# MCU089A_Connectors.net
KiCad netlist of a schematic drawn in Altium Designer
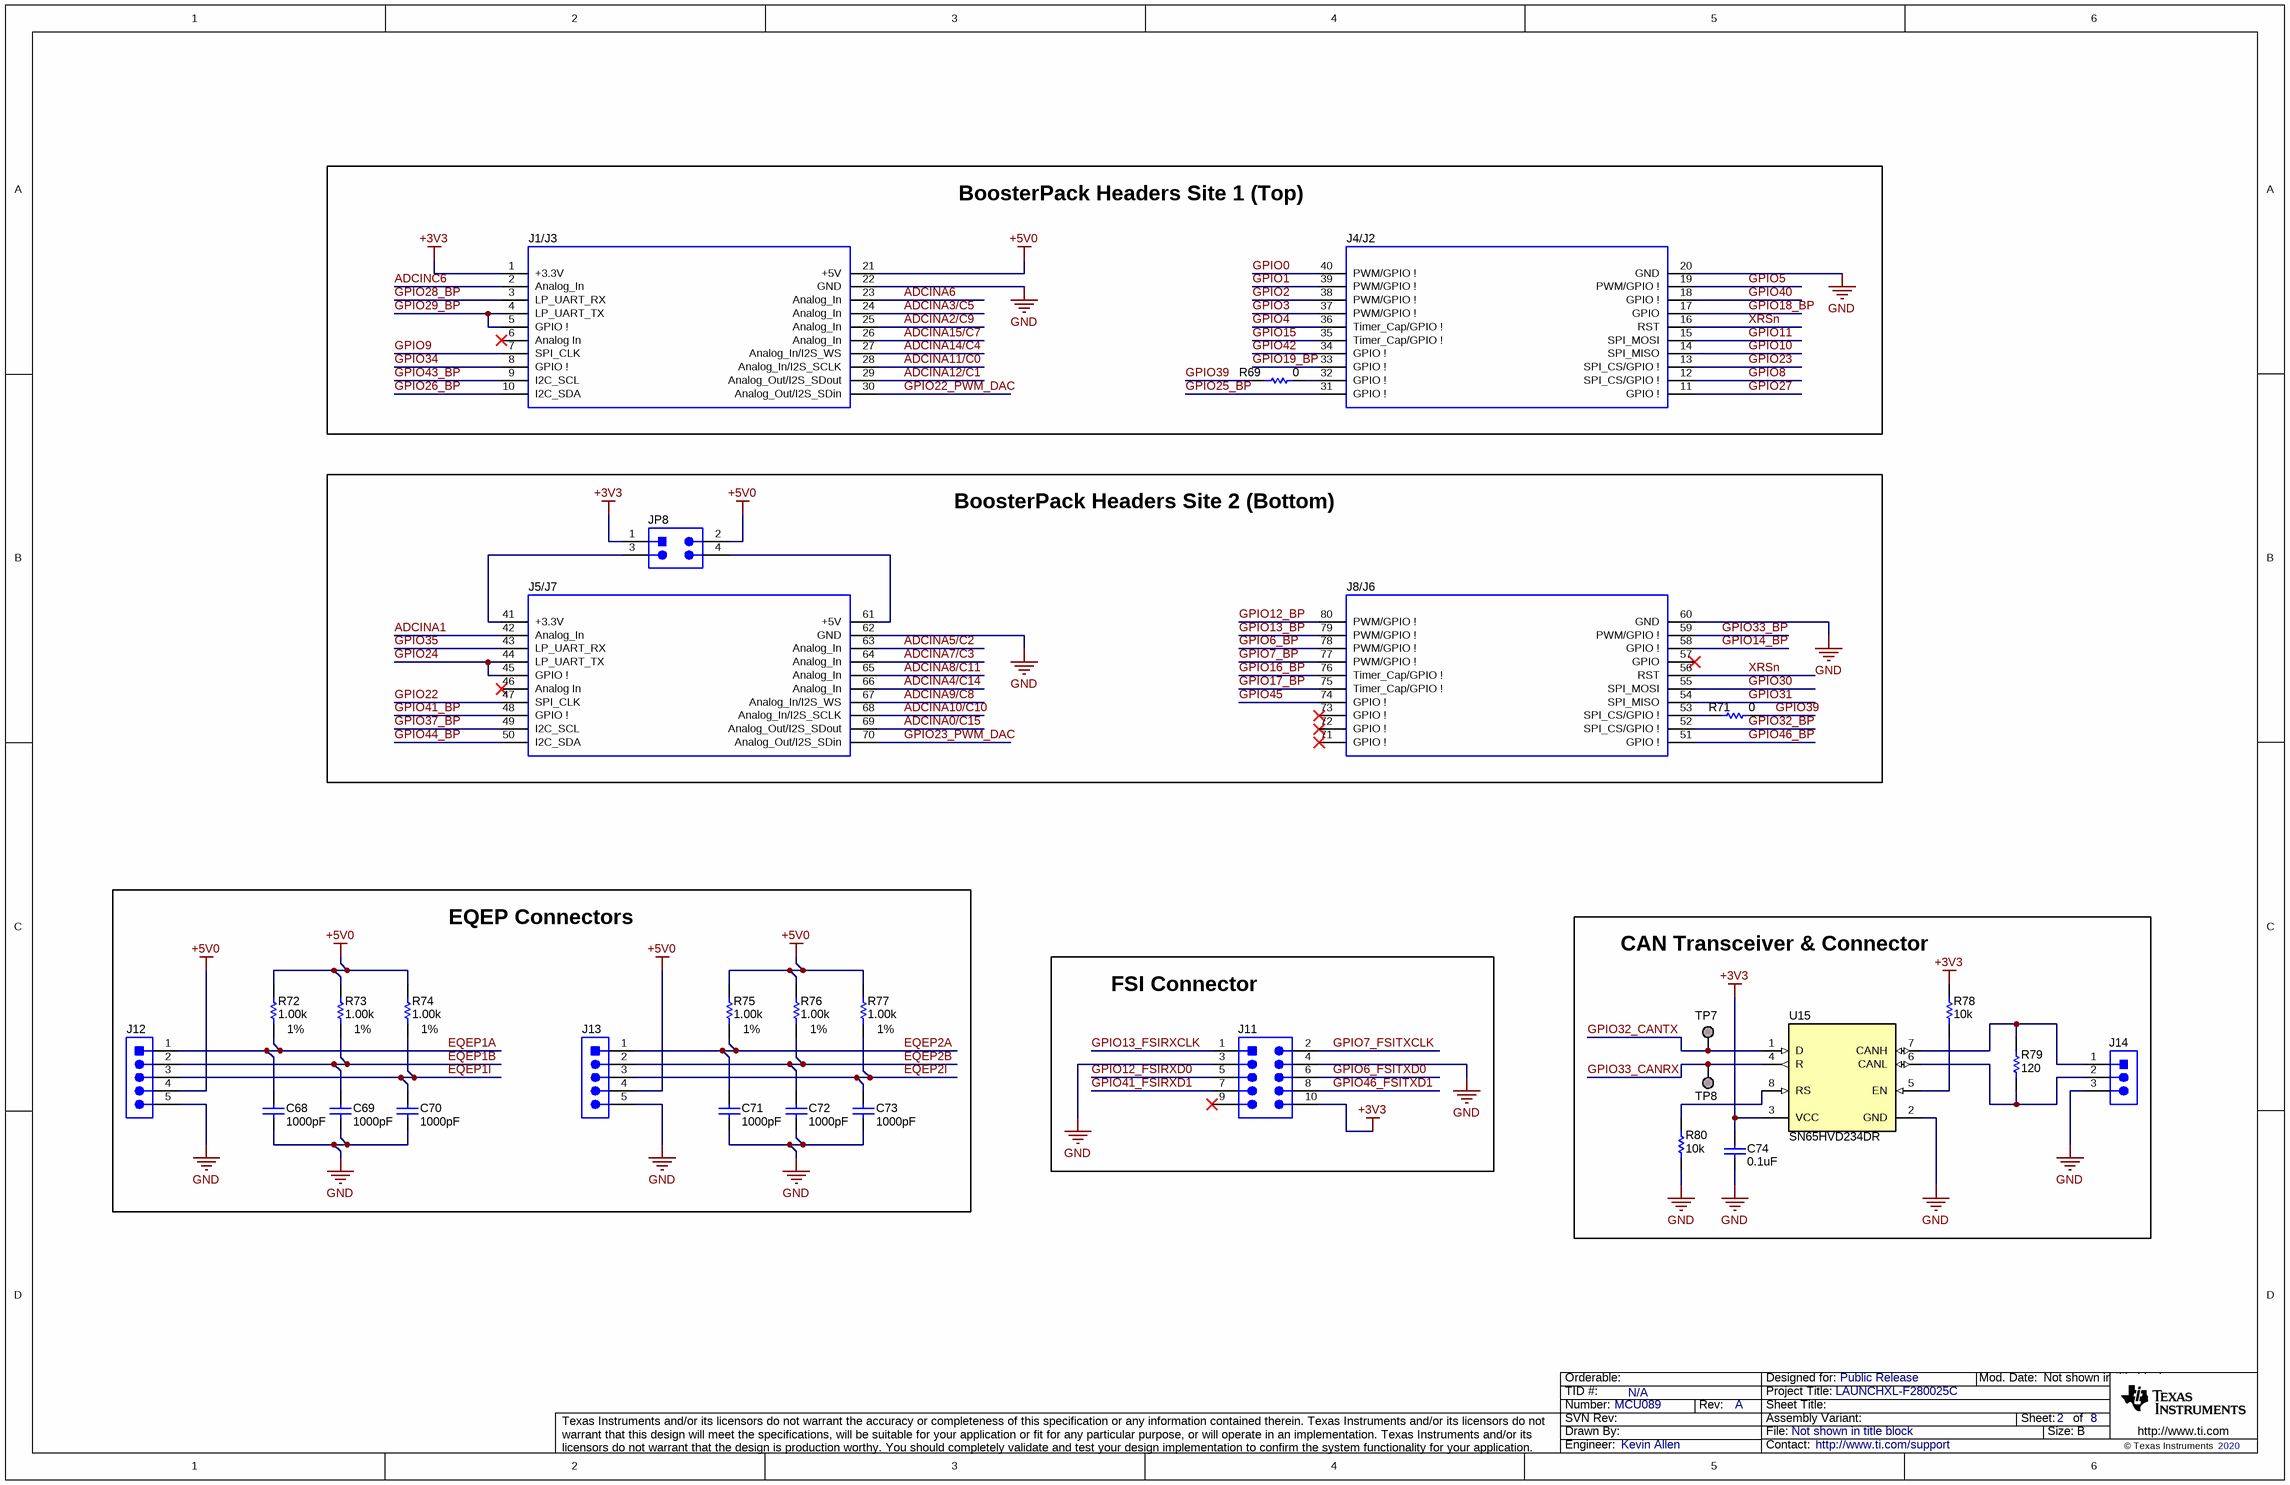
[diagram p0: MCU089A_Connectors.SchDoc]

(export (version "E")
  (design (tool "Eeschema 10.0.6"))
  (components
    (comp (ref "C68")
      (value "885012205061")
      (footprint "0402")
      (description "CAP, CERM, 1000 pF, 50 V, +/- 10%, X7R, 0402")
      (fields
        (field (name "VALUEDISPLAYED") "1000pF")
        (field (name "MANUFACTURER") "Wurth Elektronik")
        (field (name "PUBLISHER") "Texas Instruments")
      )
      (libsource (lib "Altium Vault - TI") (part "Capacitor"))
    )
    (comp (ref "C69")
      (value "885012205061")
      (footprint "0402")
      (description "CAP, CERM, 1000 pF, 50 V, +/- 10%, X7R, 0402")
      (fields
        (field (name "VALUEDISPLAYED") "1000pF")
        (field (name "MANUFACTURER") "Wurth Elektronik")
        (field (name "PUBLISHER") "Texas Instruments")
      )
      (libsource (lib "Altium Vault - TI") (part "Capacitor"))
    )
    (comp (ref "C70")
      (value "885012205061")
      (footprint "0402")
      (description "CAP, CERM, 1000 pF, 50 V, +/- 10%, X7R, 0402")
      (fields
        (field (name "VALUEDISPLAYED") "1000pF")
        (field (name "MANUFACTURER") "Wurth Elektronik")
        (field (name "PUBLISHER") "Texas Instruments")
      )
      (libsource (lib "Altium Vault - TI") (part "Capacitor"))
    )
    (comp (ref "C71")
      (value "885012205061")
      (footprint "0402")
      (description "CAP, CERM, 1000 pF, 50 V, +/- 10%, X7R, 0402")
      (fields
        (field (name "VALUEDISPLAYED") "1000pF")
        (field (name "MANUFACTURER") "Wurth Elektronik")
        (field (name "PUBLISHER") "Texas Instruments")
      )
      (libsource (lib "Altium Vault - TI") (part "Capacitor"))
    )
    (comp (ref "C72")
      (value "885012205061")
      (footprint "0402")
      (description "CAP, CERM, 1000 pF, 50 V, +/- 10%, X7R, 0402")
      (fields
        (field (name "VALUEDISPLAYED") "1000pF")
        (field (name "MANUFACTURER") "Wurth Elektronik")
        (field (name "PUBLISHER") "Texas Instruments")
      )
      (libsource (lib "Altium Vault - TI") (part "Capacitor"))
    )
    (comp (ref "C73")
      (value "885012205061")
      (footprint "0402")
      (description "CAP, CERM, 1000 pF, 50 V, +/- 10%, X7R, 0402")
      (fields
        (field (name "VALUEDISPLAYED") "1000pF")
        (field (name "MANUFACTURER") "Wurth Elektronik")
        (field (name "PUBLISHER") "Texas Instruments")
      )
      (libsource (lib "Altium Vault - TI") (part "Capacitor"))
    )
    (comp (ref "C74")
      (value "GRM155R71A104KA01D")
      (footprint "0402")
      (description "CAP, CERM, 0.1 uF, 10 V, +/- 10%, X7R, 0402")
      (fields
        (field (name "VALUEDISPLAYED") "0.1uF")
        (field (name "MANUFACTURER") "MuRata")
        (field (name "PUBLISHER") "Texas Instruments")
      )
      (libsource (lib "Altium Vault - TI") (part "Capacitor"))
    )
    (comp (ref "J1/J3")
      (value "SSQ-110-03-T-D")
      (footprint "BoosterPack_40pin_J1J3")
      (description "Receptacle, 2.54mm, 10x2, Tin, TH")
      (fields (field (name "ALTERNATE PARTNUMBER") "CRD-081413-A-G") (field (name "MANUFACTURER") "Samtec"))
      (libsource (lib "Altium Vault - TI") (part "BoosterPack_40pin_J1J3"))
    )
    (comp (ref "J4/J2")
      (value "SSQ-110-03-T-D")
      (footprint "BoosterPack_40pin_J2J4")
      (description "Receptacle, 2.54mm, 10x2, Tin, TH")
      (fields (field (name "ALTERNATE PARTNUMBER") "CRD-081413-A-G") (field (name "MANUFACTURER") "Samtec"))
      (libsource (lib "Altium Vault - TI") (part "BoosterPack_40pin_J2J4"))
    )
    (comp (ref "J5/J7")
      (value "SSQ-110-03-T-D")
      (footprint "BoosterPack_40pin_J5J7")
      (description "Receptacle, 2.54mm, 10x2, Tin, TH")
      (fields (field (name "ALTERNATE PARTNUMBER") "CRD-081413-A-G") (field (name "MANUFACTURER") "Samtec"))
      (libsource (lib "Altium Vault - TI") (part "BoosterPack_40pin_J5J7"))
    )
    (comp (ref "J8/J6")
      (value "SSQ-110-03-T-D")
      (footprint "BoosterPack_40pin_J6J8")
      (description "Receptacle, 2.54mm, 10x2, Tin, TH")
      (fields (field (name "ALTERNATE PARTNUMBER") "CRD-081413-A-G") (field (name "MANUFACTURER") "Samtec"))
      (libsource (lib "Altium Vault - TI") (part "BoosterPack_40pin_J6J8"))
    )
    (comp (ref "J11")
      (value "TSW-105-07-G-D")
      (footprint "TSW-105-07-G-D")
      (description "Header, 100mil, 5x2, Gold, TH")
      (fields (field (name "MANUFACTURER") "Samtec"))
      (libsource (lib "Altium Vault - TI") (part "Header_5x2"))
    )
    (comp (ref "J12")
      (value "TSW-105-07-G-S")
      (footprint "TSW-105-07-X-S")
      (description "Header, 100mil, 5x1, Gold, TH")
      (fields (field (name "MANUFACTURER") "Samtec") (field (name "PUBLISHER") "Texas Instruments"))
      (libsource (lib "Altium Vault - TI") (part "Header_5x1"))
    )
    (comp (ref "J13")
      (value "TSW-105-07-G-S")
      (footprint "TSW-105-07-X-S")
      (description "Header, 100mil, 5x1, Gold, TH")
      (fields (field (name "MANUFACTURER") "Samtec") (field (name "PUBLISHER") "Texas Instruments"))
      (libsource (lib "Altium Vault - TI") (part "Header_5x1"))
    )
    (comp (ref "J14")
      (value "61300311121")
      (footprint "WURTH_61300311121")
      (description "Header, 2.54 mm, 3x1, Gold, TH")
      (fields (field (name "MANUFACTURER") "Wurth Elektronik") (field (name "PUBLISHER") "Texas Instruments"))
      (libsource (lib "Altium Vault - TI") (part "CMP-0054796-1"))
    )
    (comp (ref "JP8")
      (value "TSW-102-07-G-D")
      (footprint "TSW-102-07-G-D")
      (description "Header, 100mil, 2x2, Gold, TH")
      (fields (field (name "MANUFACTURER") "Samtec") (field (name "PUBLISHER") "Texas Instruments"))
      (libsource (lib "Altium Vault - TI") (part "Header_2x2"))
    )
    (comp (ref "R69")
      (value "CRCW06030000Z0EA")
      (footprint "0603")
      (description "RES, 0, 5%, 0.1 W, AEC-Q200 Grade 0, 0603")
      (fields (field (name "VALUEDISPLAYED") "0") (field (name "MANUFACTURER") "Vishay-Dale"))
      (libsource (lib "Altium Vault - TI") (part "Resistor"))
    )
    (comp (ref "R71")
      (value "CRCW06030000Z0EA")
      (footprint "0603")
      (description "RES, 0, 5%, 0.1 W, AEC-Q200 Grade 0, 0603")
      (fields (field (name "VALUEDISPLAYED") "0") (field (name "MANUFACTURER") "Vishay-Dale"))
      (libsource (lib "Altium Vault - TI") (part "Resistor"))
    )
    (comp (ref "R72")
      (value "CRCW04021K00FKED")
      (footprint "0402")
      (description "RES, 1.00 k, 1%, 0.063 W, AEC-Q200 Grade 0, 0402")
      (fields
        (field (name "VALUEDISPLAYED") "1.00k")
        (field (name "MANUFACTURER") "Vishay-Dale")
        (field (name "VALUE1") "1%")
      )
      (libsource (lib "Altium Vault - TI") (part "Resistor"))
    )
    (comp (ref "R73")
      (value "CRCW04021K00FKED")
      (footprint "0402")
      (description "RES, 1.00 k, 1%, 0.063 W, AEC-Q200 Grade 0, 0402")
      (fields
        (field (name "VALUEDISPLAYED") "1.00k")
        (field (name "MANUFACTURER") "Vishay-Dale")
        (field (name "VALUE1") "1%")
      )
      (libsource (lib "Altium Vault - TI") (part "Resistor"))
    )
    (comp (ref "R74")
      (value "CRCW04021K00FKED")
      (footprint "0402")
      (description "RES, 1.00 k, 1%, 0.063 W, AEC-Q200 Grade 0, 0402")
      (fields
        (field (name "VALUEDISPLAYED") "1.00k")
        (field (name "MANUFACTURER") "Vishay-Dale")
        (field (name "VALUE1") "1%")
      )
      (libsource (lib "Altium Vault - TI") (part "Resistor"))
    )
    (comp (ref "R75")
      (value "CRCW04021K00FKED")
      (footprint "0402")
      (description "RES, 1.00 k, 1%, 0.063 W, AEC-Q200 Grade 0, 0402")
      (fields
        (field (name "VALUEDISPLAYED") "1.00k")
        (field (name "MANUFACTURER") "Vishay-Dale")
        (field (name "VALUE1") "1%")
      )
      (libsource (lib "Altium Vault - TI") (part "Resistor"))
    )
    (comp (ref "R76")
      (value "CRCW04021K00FKED")
      (footprint "0402")
      (description "RES, 1.00 k, 1%, 0.063 W, AEC-Q200 Grade 0, 0402")
      (fields
        (field (name "VALUEDISPLAYED") "1.00k")
        (field (name "MANUFACTURER") "Vishay-Dale")
        (field (name "VALUE1") "1%")
      )
      (libsource (lib "Altium Vault - TI") (part "Resistor"))
    )
    (comp (ref "R77")
      (value "CRCW04021K00FKED")
      (footprint "0402")
      (description "RES, 1.00 k, 1%, 0.063 W, AEC-Q200 Grade 0, 0402")
      (fields
        (field (name "VALUEDISPLAYED") "1.00k")
        (field (name "MANUFACTURER") "Vishay-Dale")
        (field (name "VALUE1") "1%")
      )
      (libsource (lib "Altium Vault - TI") (part "Resistor"))
    )
    (comp (ref "R78")
      (value "CRCW040210K0JNED")
      (footprint "0402")
      (description "RES, 10 k, 5%, 0.063 W, AEC-Q200 Grade 0, 0402")
      (fields (field (name "VALUEDISPLAYED") "10k") (field (name "MANUFACTURER") "Vishay-Dale"))
      (libsource (lib "Altium Vault - TI") (part "Resistor"))
    )
    (comp (ref "R79")
      (value "RC0603FR-07120RL")
      (footprint "0603")
      (description "RES, 120, 1%, 0.1 W, 0603")
      (fields
        (field (name "VALUEDISPLAYED") "120")
        (field (name "MANUFACTURER") "Yageo America")
        (field (name "PUBLISHER") "Texas Instruments")
      )
      (libsource (lib "Altium Vault - TI") (part "Resistor"))
    )
    (comp (ref "R80")
      (value "CRCW040210K0JNED")
      (footprint "0402")
      (description "RES, 10 k, 5%, 0.063 W, AEC-Q200 Grade 0, 0402")
      (fields (field (name "VALUEDISPLAYED") "10k") (field (name "MANUFACTURER") "Vishay-Dale"))
      (libsource (lib "Altium Vault - TI") (part "Resistor"))
    )
    (comp (ref "TP7")
      (value "TESTPOINT")
      (footprint "TP_50MIL-25MILHOLE")
      (description "TEST POINT.  No entry in BOM.")
      (libsource (lib "Altium Vault - TI") (part "TESTPOINT"))
    )
    (comp (ref "TP8")
      (value "TESTPOINT")
      (footprint "TP_50MIL-25MILHOLE")
      (description "TEST POINT.  No entry in BOM.")
      (libsource (lib "Altium Vault - TI") (part "TESTPOINT"))
    )
    (comp (ref "U15")
      (value "SN65HVD234DR")
      (footprint "D0008A_L")
      (fields (field (name "MANUFACTURER") "Texas Instruments"))
      (libsource (lib "Altium Vault - TI") (part "TI-SN65HVD234-SOIC_D-8"))
    )
  )
  (nets
    (net (code "1") (name "+3V3") (class "Default")
      (node (ref "C74") (pin "2") (pinfunction "2_2") (pintype "passive"))
      (node (ref "J1/J3") (pin "1") (pinfunction "+3.3V_1") (pintype "power_in"))
      (node (ref "J11") (pin "10") (pinfunction "10_10") (pintype "passive"))
      (node (ref "JP8") (pin "1") (pinfunction "1_1") (pintype "passive"))
      (node (ref "R78") (pin "2") (pinfunction "2_2") (pintype "passive"))
      (node (ref "U15") (pin "3") (pinfunction "VCC_3") (pintype "power_in"))
    )
    (net (code "2") (name "+5V0") (class "Default")
      (node (ref "J1/J3") (pin "21") (pinfunction "+5V_21") (pintype "power_in"))
      (node (ref "J12") (pin "4") (pinfunction "4_4") (pintype "passive"))
      (node (ref "J13") (pin "4") (pinfunction "4_4") (pintype "passive"))
      (node (ref "JP8") (pin "2") (pinfunction "2_2") (pintype "passive"))
      (node (ref "R72") (pin "2") (pinfunction "2_2") (pintype "passive"))
      (node (ref "R73") (pin "2") (pinfunction "2_2") (pintype "passive"))
      (node (ref "R74") (pin "2") (pinfunction "2_2") (pintype "passive"))
      (node (ref "R75") (pin "2") (pinfunction "2_2") (pintype "passive"))
      (node (ref "R76") (pin "2") (pinfunction "2_2") (pintype "passive"))
      (node (ref "R77") (pin "2") (pinfunction "2_2") (pintype "passive"))
    )
    (net (code "3") (name "/ADCINA0{slash}C15") (class "Default")
      (node (ref "J5/J7") (pin "69") (pinfunction "Analog_Out/I2S_SDout_69") (pintype "passive"))
    )
    (net (code "4") (name "/ADCINA1") (class "Default")
      (node (ref "J5/J7") (pin "42") (pinfunction "Analog_In_42") (pintype "passive"))
    )
    (net (code "5") (name "/ADCINA2{slash}C9") (class "Default")
      (node (ref "J1/J3") (pin "25") (pinfunction "Analog_In_25") (pintype "passive"))
    )
    (net (code "6") (name "/ADCINA3{slash}C5") (class "Default")
      (node (ref "J1/J3") (pin "24") (pinfunction "Analog_In_24") (pintype "passive"))
    )
    (net (code "7") (name "/ADCINA4{slash}C14") (class "Default")
      (node (ref "J5/J7") (pin "66") (pinfunction "Analog_In_66") (pintype "passive"))
    )
    (net (code "8") (name "/ADCINA5{slash}C2") (class "Default")
      (node (ref "J5/J7") (pin "63") (pinfunction "Analog_In_63") (pintype "passive"))
    )
    (net (code "9") (name "/ADCINA6") (class "Default")
      (node (ref "J1/J3") (pin "23") (pinfunction "Analog_In_23") (pintype "passive"))
    )
    (net (code "10") (name "/ADCINA7{slash}C3") (class "Default")
      (node (ref "J5/J7") (pin "64") (pinfunction "Analog_In_64") (pintype "passive"))
    )
    (net (code "11") (name "/ADCINA8{slash}C11") (class "Default")
      (node (ref "J5/J7") (pin "65") (pinfunction "Analog_In_65") (pintype "passive"))
    )
    (net (code "12") (name "/ADCINA9{slash}C8") (class "Default")
      (node (ref "J5/J7") (pin "67") (pinfunction "Analog_In/I2S_WS_67") (pintype "passive"))
    )
    (net (code "13") (name "/ADCINA10{slash}C10") (class "Default")
      (node (ref "J5/J7") (pin "68") (pinfunction "Analog_In/I2S_SCLK_68") (pintype "passive"))
    )
    (net (code "14") (name "/ADCINA11{slash}C0") (class "Default")
      (node (ref "J1/J3") (pin "28") (pinfunction "Analog_In/I2S_SCLK_28") (pintype "passive"))
    )
    (net (code "15") (name "/ADCINA12{slash}C1") (class "Default")
      (node (ref "J1/J3") (pin "29") (pinfunction "Analog_Out/I2S_SDout_29") (pintype "passive"))
    )
    (net (code "16") (name "/ADCINA14{slash}C4") (class "Default")
      (node (ref "J1/J3") (pin "27") (pinfunction "Analog_In/I2S_WS_27") (pintype "passive"))
    )
    (net (code "17") (name "/ADCINA15{slash}C7") (class "Default")
      (node (ref "J1/J3") (pin "26") (pinfunction "Analog_In_26") (pintype "passive"))
    )
    (net (code "18") (name "/ADCINC6") (class "Default")
      (node (ref "J1/J3") (pin "2") (pinfunction "Analog_In_2") (pintype "passive"))
    )
    (net (code "19") (name "/EQEP1A") (class "Default")
      (node (ref "C68") (pin "1") (pinfunction "1_1") (pintype "passive"))
      (node (ref "J12") (pin "1") (pinfunction "1_1") (pintype "passive"))
      (node (ref "R72") (pin "1") (pinfunction "1_1") (pintype "passive"))
    )
    (net (code "20") (name "/EQEP1B") (class "Default")
      (node (ref "C69") (pin "1") (pinfunction "1_1") (pintype "passive"))
      (node (ref "J12") (pin "2") (pinfunction "2_2") (pintype "passive"))
      (node (ref "R73") (pin "1") (pinfunction "1_1") (pintype "passive"))
    )
    (net (code "21") (name "/EQEP1I") (class "Default")
      (node (ref "C70") (pin "1") (pinfunction "1_1") (pintype "passive"))
      (node (ref "J12") (pin "3") (pinfunction "3_3") (pintype "passive"))
      (node (ref "R74") (pin "1") (pinfunction "1_1") (pintype "passive"))
    )
    (net (code "22") (name "/EQEP2A") (class "Default")
      (node (ref "C71") (pin "1") (pinfunction "1_1") (pintype "passive"))
      (node (ref "J13") (pin "1") (pinfunction "1_1") (pintype "passive"))
      (node (ref "R75") (pin "1") (pinfunction "1_1") (pintype "passive"))
    )
    (net (code "23") (name "/EQEP2B") (class "Default")
      (node (ref "C72") (pin "1") (pinfunction "1_1") (pintype "passive"))
      (node (ref "J13") (pin "2") (pinfunction "2_2") (pintype "passive"))
      (node (ref "R76") (pin "1") (pinfunction "1_1") (pintype "passive"))
    )
    (net (code "24") (name "/EQEP2I") (class "Default")
      (node (ref "C73") (pin "1") (pinfunction "1_1") (pintype "passive"))
      (node (ref "J13") (pin "3") (pinfunction "3_3") (pintype "passive"))
      (node (ref "R77") (pin "1") (pinfunction "1_1") (pintype "passive"))
    )
    (net (code "25") (name "/GPIO0") (class "Default")
      (node (ref "J4/J2") (pin "40") (pinfunction "PWM/GPIO_!_40") (pintype "passive"))
    )
    (net (code "26") (name "/GPIO1") (class "Default")
      (node (ref "J4/J2") (pin "39") (pinfunction "PWM/GPIO_!_39") (pintype "passive"))
    )
    (net (code "27") (name "/GPIO2") (class "Default")
      (node (ref "J4/J2") (pin "38") (pinfunction "PWM/GPIO_!_38") (pintype "passive"))
    )
    (net (code "28") (name "/GPIO3") (class "Default")
      (node (ref "J4/J2") (pin "37") (pinfunction "PWM/GPIO_!_37") (pintype "passive"))
    )
    (net (code "29") (name "/GPIO4") (class "Default")
      (node (ref "J4/J2") (pin "36") (pinfunction "Timer_Cap/GPIO_!_36") (pintype "passive"))
    )
    (net (code "30") (name "/GPIO5") (class "Default")
      (node (ref "J4/J2") (pin "19") (pinfunction "PWM/GPIO_!_19") (pintype "passive"))
    )
    (net (code "31") (name "/GPIO6_BP") (class "Default")
      (node (ref "J8/J6") (pin "78") (pinfunction "PWM/GPIO_!_78") (pintype "passive"))
    )
    (net (code "32") (name "/GPIO6_FSITXD0") (class "Default")
      (node (ref "J11") (pin "6") (pinfunction "6_6") (pintype "passive"))
    )
    (net (code "33") (name "/GPIO7_BP") (class "Default")
      (node (ref "J8/J6") (pin "77") (pinfunction "PWM/GPIO_!_77") (pintype "passive"))
    )
    (net (code "34") (name "/GPIO7_FSITXCLK") (class "Default")
      (node (ref "J11") (pin "2") (pinfunction "2_2") (pintype "passive"))
    )
    (net (code "35") (name "/GPIO8") (class "Default")
      (node (ref "J4/J2") (pin "12") (pinfunction "SPI_CS/GPIO_!_12") (pintype "passive"))
    )
    (net (code "36") (name "/GPIO9") (class "Default")
      (node (ref "J1/J3") (pin "7") (pinfunction "SPI_CLK_7") (pintype "passive"))
    )
    (net (code "37") (name "/GPIO10") (class "Default")
      (node (ref "J4/J2") (pin "14") (pinfunction "SPI_MISO_14") (pintype "passive"))
    )
    (net (code "38") (name "/GPIO11") (class "Default")
      (node (ref "J4/J2") (pin "15") (pinfunction "SPI_MOSI_15") (pintype "passive"))
    )
    (net (code "39") (name "/GPIO12_BP") (class "Default")
      (node (ref "J8/J6") (pin "80") (pinfunction "PWM/GPIO_!_80") (pintype "passive"))
    )
    (net (code "40") (name "/GPIO12_FSIRXD0") (class "Default")
      (node (ref "J11") (pin "5") (pinfunction "5_5") (pintype "passive"))
    )
    (net (code "41") (name "/GPIO13_BP") (class "Default")
      (node (ref "J8/J6") (pin "79") (pinfunction "PWM/GPIO_!_79") (pintype "passive"))
    )
    (net (code "42") (name "/GPIO13_FSIRXCLK") (class "Default")
      (node (ref "J11") (pin "1") (pinfunction "1_1") (pintype "passive"))
    )
    (net (code "43") (name "/GPIO14_BP") (class "Default")
      (node (ref "J8/J6") (pin "58") (pinfunction "GPIO_!_58") (pintype "passive"))
    )
    (net (code "44") (name "/GPIO15") (class "Default")
      (node (ref "J4/J2") (pin "35") (pinfunction "Timer_Cap/GPIO_!_35") (pintype "passive"))
    )
    (net (code "45") (name "/GPIO16_BP") (class "Default")
      (node (ref "J8/J6") (pin "76") (pinfunction "Timer_Cap/GPIO_!_76") (pintype "passive"))
    )
    (net (code "46") (name "/GPIO17_BP") (class "Default")
      (node (ref "J8/J6") (pin "75") (pinfunction "Timer_Cap/GPIO_!_75") (pintype "passive"))
    )
    (net (code "47") (name "/GPIO18_BP") (class "Default")
      (node (ref "J4/J2") (pin "17") (pinfunction "GPIO_17") (pintype "passive"))
    )
    (net (code "48") (name "/GPIO19_BP") (class "Default")
      (node (ref "J4/J2") (pin "33") (pinfunction "GPIO_!_33") (pintype "passive"))
    )
    (net (code "49") (name "/GPIO22") (class "Default")
      (node (ref "J5/J7") (pin "47") (pinfunction "SPI_CLK_47") (pintype "passive"))
    )
    (net (code "50") (name "/GPIO22_PWM_DAC") (class "Default")
      (node (ref "J1/J3") (pin "30") (pinfunction "Analog_Out/I2S_SDin_30") (pintype "passive"))
    )
    (net (code "51") (name "/GPIO23") (class "Default")
      (node (ref "J4/J2") (pin "13") (pinfunction "SPI_CS/GPIO_!_13") (pintype "passive"))
    )
    (net (code "52") (name "/GPIO23_PWM_DAC") (class "Default")
      (node (ref "J5/J7") (pin "70") (pinfunction "Analog_Out/I2S_SDin_70") (pintype "passive"))
    )
    (net (code "53") (name "/GPIO24") (class "Default")
      (node (ref "J5/J7") (pin "44") (pinfunction "LP_UART_TX_44") (pintype "passive"))
      (node (ref "J5/J7") (pin "45") (pinfunction "GPIO_!_45") (pintype "passive"))
    )
    (net (code "54") (name "/GPIO25_BP") (class "Default")
      (node (ref "J4/J2") (pin "31") (pinfunction "GPIO_!_31") (pintype "passive"))
    )
    (net (code "55") (name "/GPIO26_BP") (class "Default")
      (node (ref "J1/J3") (pin "10") (pinfunction "I2C_SDA_10") (pintype "passive"))
    )
    (net (code "56") (name "/GPIO27") (class "Default")
      (node (ref "J4/J2") (pin "11") (pinfunction "GPIO_!_11") (pintype "passive"))
    )
    (net (code "57") (name "/GPIO28_BP") (class "Default")
      (node (ref "J1/J3") (pin "3") (pinfunction "LP_UART_RX_3") (pintype "passive"))
    )
    (net (code "58") (name "/GPIO29_BP") (class "Default")
      (node (ref "J1/J3") (pin "4") (pinfunction "LP_UART_TX_4") (pintype "passive"))
      (node (ref "J1/J3") (pin "5") (pinfunction "GPIO_!_5") (pintype "passive"))
    )
    (net (code "59") (name "/GPIO30") (class "Default")
      (node (ref "J8/J6") (pin "55") (pinfunction "SPI_MOSI_55") (pintype "passive"))
    )
    (net (code "60") (name "/GPIO31") (class "Default")
      (node (ref "J8/J6") (pin "54") (pinfunction "SPI_MISO_54") (pintype "passive"))
    )
    (net (code "61") (name "/GPIO32_BP") (class "Default")
      (node (ref "J8/J6") (pin "52") (pinfunction "SPI_CS/GPIO_!_52") (pintype "passive"))
    )
    (net (code "62") (name "/GPIO32_CANTX") (class "Default")
      (node (ref "TP7") (pin "1") (pintype "passive"))
      (node (ref "U15") (pin "1") (pinfunction "D_1") (pintype "input"))
    )
    (net (code "63") (name "/GPIO33_BP") (class "Default")
      (node (ref "J8/J6") (pin "59") (pinfunction "PWM/GPIO_!_59") (pintype "passive"))
    )
    (net (code "64") (name "/GPIO33_CANRX") (class "Default")
      (node (ref "TP8") (pin "1") (pintype "passive"))
      (node (ref "U15") (pin "4") (pinfunction "R_4") (pintype "output"))
    )
    (net (code "65") (name "/GPIO34") (class "Default")
      (node (ref "J1/J3") (pin "8") (pinfunction "GPIO_!_8") (pintype "passive"))
    )
    (net (code "66") (name "/GPIO35") (class "Default")
      (node (ref "J5/J7") (pin "43") (pinfunction "LP_UART_RX_43") (pintype "passive"))
    )
    (net (code "67") (name "/GPIO37_BP") (class "Default")
      (node (ref "J5/J7") (pin "49") (pinfunction "I2C_SCL_49") (pintype "passive"))
    )
    (net (code "68") (name "/GPIO39") (class "Default")
      (node (ref "R69") (pin "1") (pinfunction "1_1") (pintype "passive"))
      (node (ref "R71") (pin "2") (pinfunction "2_2") (pintype "passive"))
    )
    (net (code "69") (name "/GPIO40") (class "Default")
      (node (ref "J4/J2") (pin "18") (pinfunction "GPIO_!_18") (pintype "passive"))
    )
    (net (code "70") (name "/GPIO41_BP") (class "Default")
      (node (ref "J5/J7") (pin "48") (pinfunction "GPIO_!_48") (pintype "passive"))
    )
    (net (code "71") (name "/GPIO41_FSIRXD1") (class "Default")
      (node (ref "J11") (pin "7") (pinfunction "7_7") (pintype "passive"))
    )
    (net (code "72") (name "/GPIO42") (class "Default")
      (node (ref "J4/J2") (pin "34") (pinfunction "GPIO_!_34") (pintype "passive"))
    )
    (net (code "73") (name "/GPIO43_BP") (class "Default")
      (node (ref "J1/J3") (pin "9") (pinfunction "I2C_SCL_9") (pintype "passive"))
    )
    (net (code "74") (name "/GPIO44_BP") (class "Default")
      (node (ref "J5/J7") (pin "50") (pinfunction "I2C_SDA_50") (pintype "passive"))
    )
    (net (code "75") (name "/GPIO45") (class "Default")
      (node (ref "J8/J6") (pin "74") (pinfunction "GPIO_!_74") (pintype "passive"))
    )
    (net (code "76") (name "/GPIO46_BP") (class "Default")
      (node (ref "J8/J6") (pin "51") (pinfunction "GPIO_!_51") (pintype "passive"))
    )
    (net (code "77") (name "/GPIO46_FSITXD1") (class "Default")
      (node (ref "J11") (pin "8") (pinfunction "8_8") (pintype "passive"))
    )
    (net (code "78") (name "/XRSn") (class "Default")
      (node (ref "J4/J2") (pin "16") (pinfunction "RST_16") (pintype "passive"))
      (node (ref "J8/J6") (pin "56") (pinfunction "RST_56") (pintype "passive"))
    )
    (net (code "79") (name "GND") (class "Default")
      (node (ref "C68") (pin "2") (pinfunction "2_2") (pintype "passive"))
      (node (ref "C69") (pin "2") (pinfunction "2_2") (pintype "passive"))
      (node (ref "C70") (pin "2") (pinfunction "2_2") (pintype "passive"))
      (node (ref "C71") (pin "2") (pinfunction "2_2") (pintype "passive"))
      (node (ref "C72") (pin "2") (pinfunction "2_2") (pintype "passive"))
      (node (ref "C73") (pin "2") (pinfunction "2_2") (pintype "passive"))
      (node (ref "C74") (pin "1") (pinfunction "1_1") (pintype "passive"))
      (node (ref "J1/J3") (pin "22") (pinfunction "GND_22") (pintype "power_in"))
      (node (ref "J11") (pin "3") (pinfunction "3_3") (pintype "passive"))
      (node (ref "J11") (pin "4") (pinfunction "4_4") (pintype "passive"))
      (node (ref "J12") (pin "5") (pinfunction "5_5") (pintype "passive"))
      (node (ref "J13") (pin "5") (pinfunction "5_5") (pintype "passive"))
      (node (ref "J14") (pin "3") (pinfunction "3_3") (pintype "passive"))
      (node (ref "J4/J2") (pin "20") (pinfunction "GND_20") (pintype "power_in"))
      (node (ref "J5/J7") (pin "62") (pinfunction "GND_62") (pintype "power_in"))
      (node (ref "J8/J6") (pin "60") (pinfunction "GND_60") (pintype "power_in"))
      (node (ref "R80") (pin "1") (pinfunction "1_1") (pintype "passive"))
      (node (ref "U15") (pin "2") (pinfunction "GND_2") (pintype "power_in"))
    )
    (net (code "80") (name "Net-(J4/J2-GPIO_!-Pad32)") (class "Default")
      (node (ref "J4/J2") (pin "32") (pinfunction "GPIO_!_32") (pintype "passive"))
      (node (ref "R69") (pin "2") (pinfunction "2_2") (pintype "passive"))
    )
    (net (code "81") (name "Net-(J5/J7-+3.3V)") (class "Default")
      (node (ref "J5/J7") (pin "41") (pinfunction "+3.3V_41") (pintype "power_in"))
      (node (ref "JP8") (pin "3") (pinfunction "3_3") (pintype "passive"))
    )
    (net (code "82") (name "Net-(J5/J7-+5V)") (class "Default")
      (node (ref "J5/J7") (pin "61") (pinfunction "+5V_61") (pintype "power_in"))
      (node (ref "JP8") (pin "4") (pinfunction "4_4") (pintype "passive"))
    )
    (net (code "83") (name "Net-(J8/J6-SPI_CS{slash}GPIO_!-Pad53)") (class "Default")
      (node (ref "J8/J6") (pin "53") (pinfunction "SPI_CS/GPIO_!_53") (pintype "passive"))
      (node (ref "R71") (pin "1") (pinfunction "1_1") (pintype "passive"))
    )
    (net (code "84") (name "Net-(U15-CANH)") (class "Default")
      (node (ref "J14") (pin "1") (pinfunction "1_1") (pintype "passive"))
      (node (ref "R79") (pin "2") (pinfunction "2_2") (pintype "passive"))
      (node (ref "U15") (pin "7") (pinfunction "CANH_7") (pintype "bidirectional"))
    )
    (net (code "85") (name "Net-(U15-CANL)") (class "Default")
      (node (ref "J14") (pin "2") (pinfunction "2_2") (pintype "passive"))
      (node (ref "R79") (pin "1") (pinfunction "1_1") (pintype "passive"))
      (node (ref "U15") (pin "6") (pinfunction "CANL_6") (pintype "bidirectional"))
    )
    (net (code "86") (name "Net-(U15-EN)") (class "Default")
      (node (ref "R78") (pin "1") (pinfunction "1_1") (pintype "passive"))
      (node (ref "U15") (pin "5") (pinfunction "EN_5") (pintype "input"))
    )
    (net (code "87") (name "Net-(U15-RS)") (class "Default")
      (node (ref "R80") (pin "2") (pinfunction "2_2") (pintype "passive"))
      (node (ref "U15") (pin "8") (pinfunction "RS_8") (pintype "input"))
    )
    (net (code "88") (name "unconnected-(J1/J3-Analog_In-Pad6)") (class "Default")
      (node (ref "J1/J3") (pin "6") (pinfunction "Analog_In_6") (pintype "passive+no_connect"))
    )
    (net (code "89") (name "unconnected-(J5/J7-Analog_In-Pad46)") (class "Default")
      (node (ref "J5/J7") (pin "46") (pinfunction "Analog_In_46") (pintype "passive+no_connect"))
    )
    (net (code "90") (name "unconnected-(J8/J6-GPIO-Pad57)") (class "Default")
      (node (ref "J8/J6") (pin "57") (pinfunction "GPIO_57") (pintype "passive+no_connect"))
    )
    (net (code "91") (name "unconnected-(J8/J6-GPIO_!-Pad71)") (class "Default")
      (node (ref "J8/J6") (pin "71") (pinfunction "GPIO_!_71") (pintype "passive+no_connect"))
    )
    (net (code "92") (name "unconnected-(J8/J6-GPIO_!-Pad72)") (class "Default")
      (node (ref "J8/J6") (pin "72") (pinfunction "GPIO_!_72") (pintype "passive+no_connect"))
    )
    (net (code "93") (name "unconnected-(J8/J6-GPIO_!-Pad73)") (class "Default")
      (node (ref "J8/J6") (pin "73") (pinfunction "GPIO_!_73") (pintype "passive+no_connect"))
    )
    (net (code "94") (name "unconnected-(J11-Pad9)") (class "Default")
      (node (ref "J11") (pin "9") (pinfunction "9_9") (pintype "passive+no_connect"))
    )
  )
)
